# arduinolcd_2020-11-17_19-29-00.net
KiCad netlist of a schematic drawn in EasyEDA
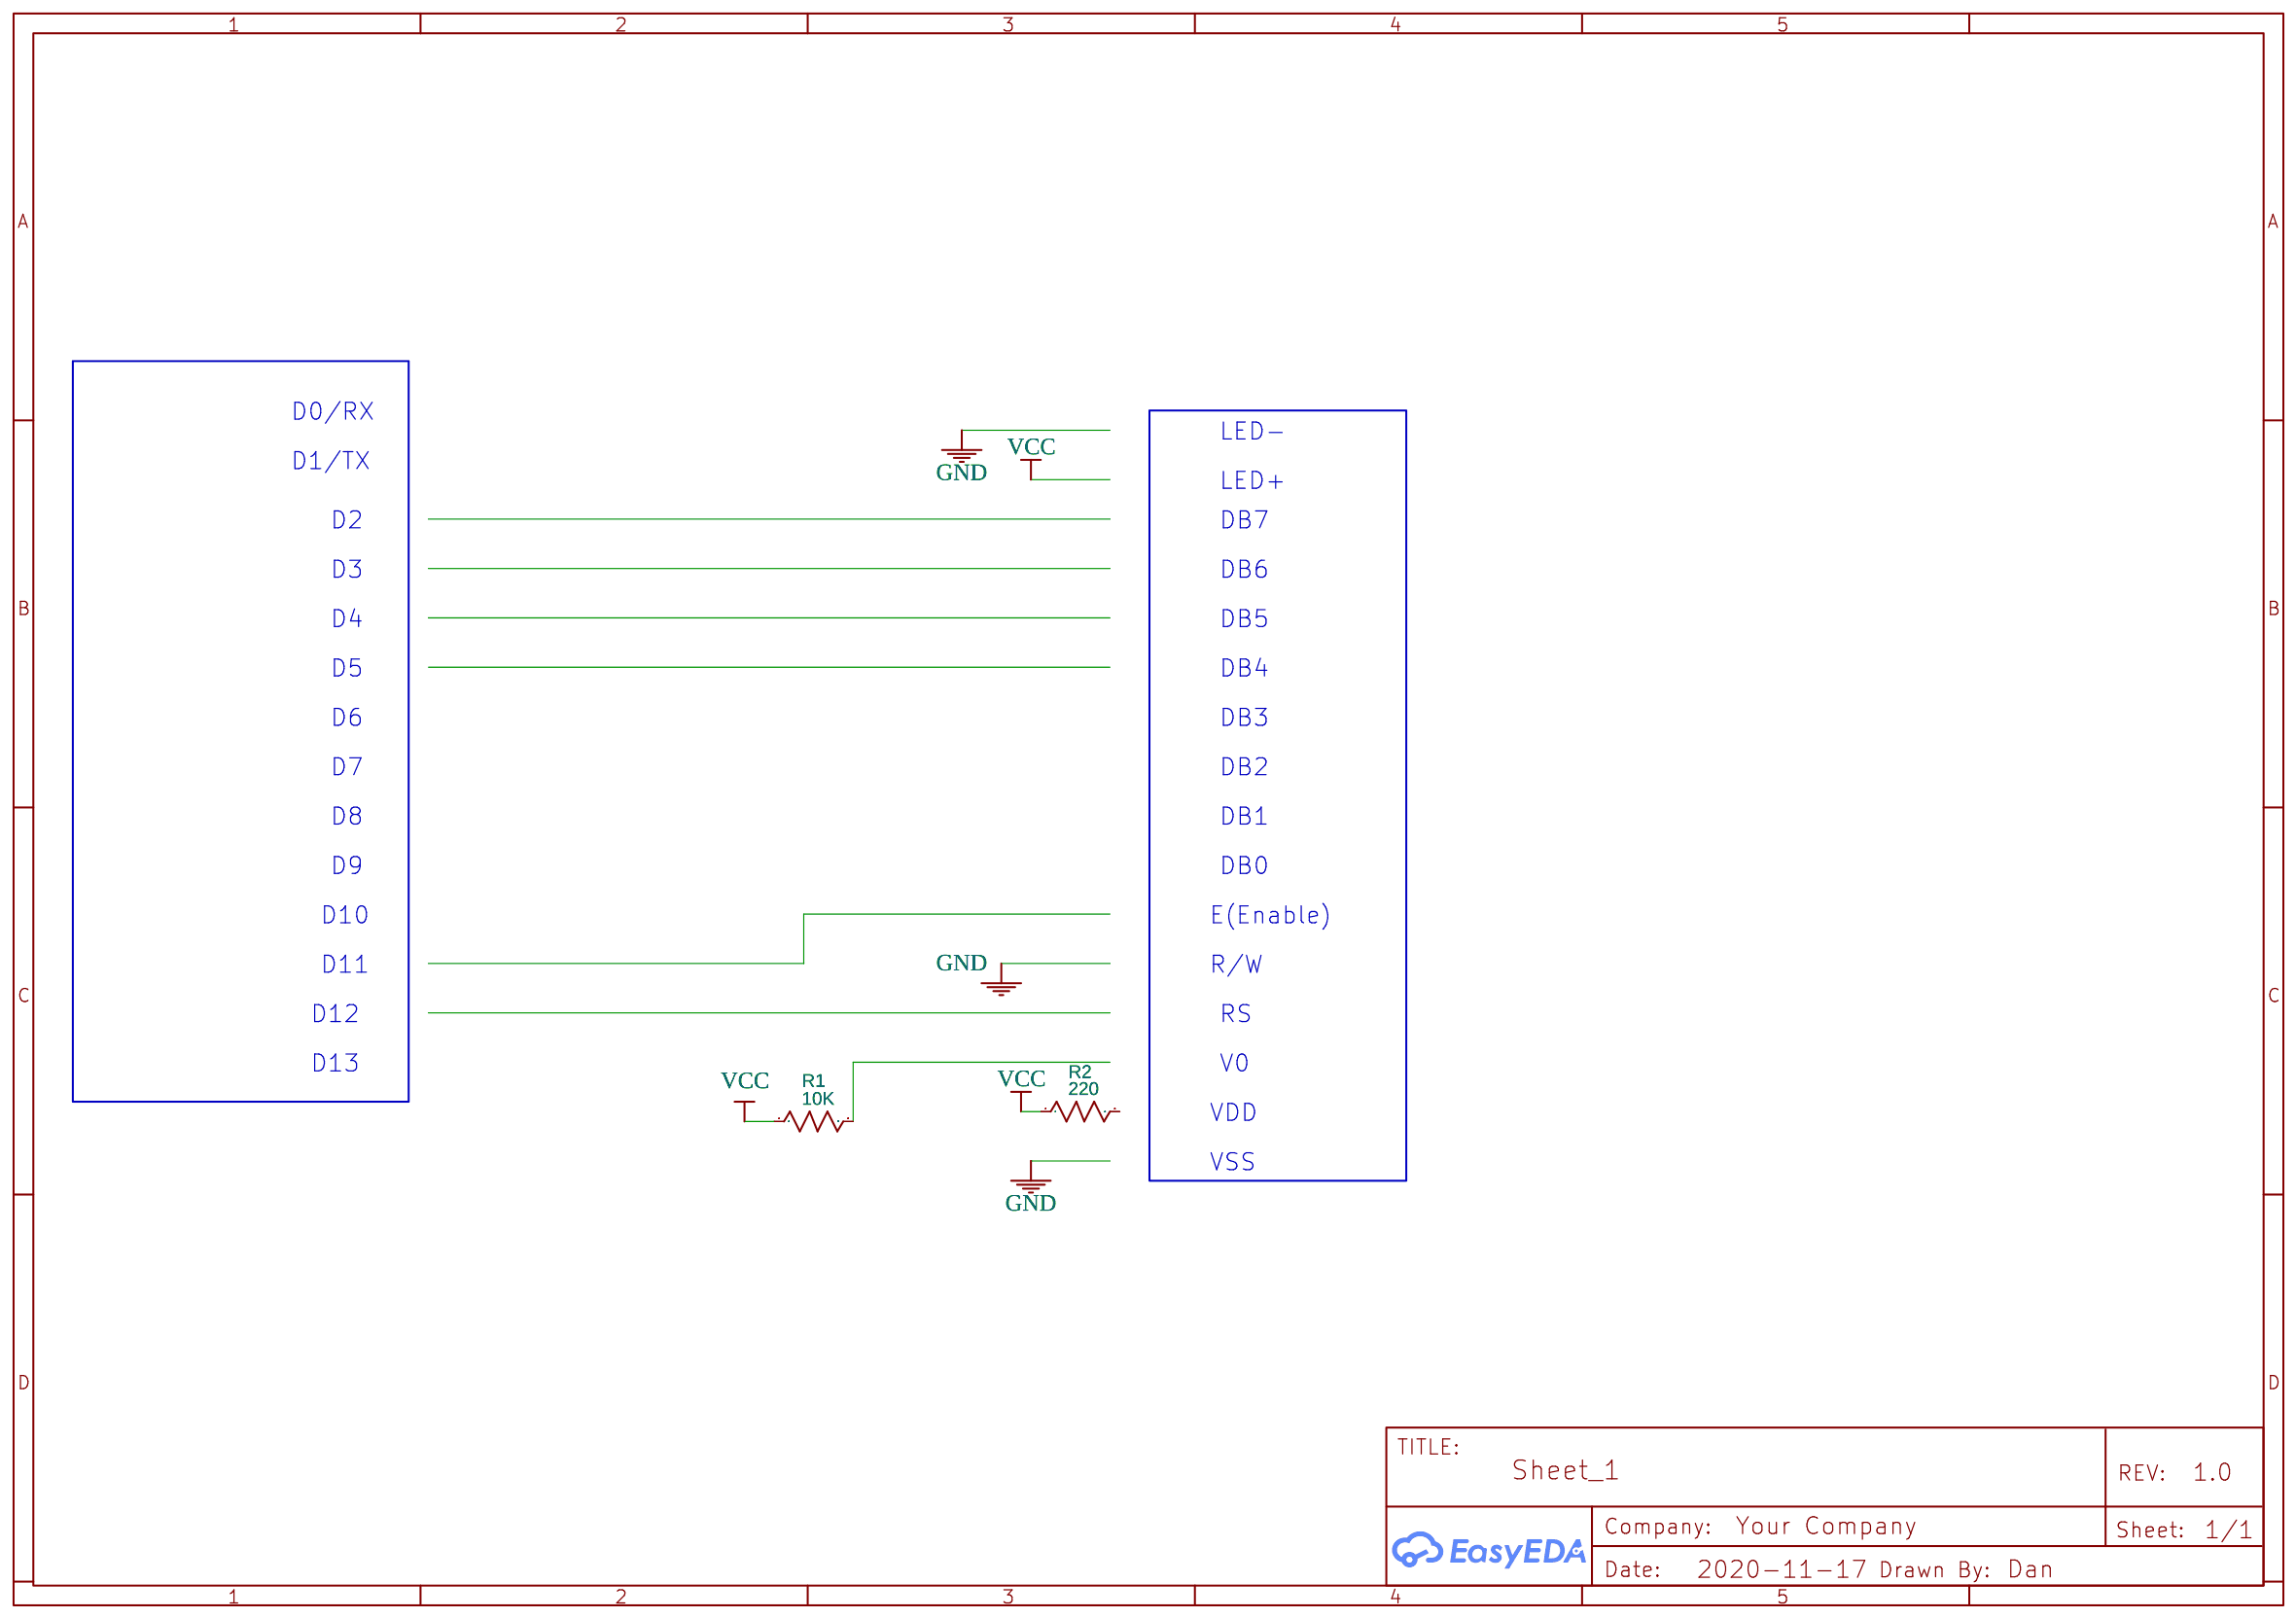
[diagram p0: schematic sheet]

(export (version "E")
  (design (tool "Eeschema 10.0.6"))
  (components
    (comp (ref "R1") (value "10K") (libsource (lib "") (part "R_0603_US")))
    (comp (ref "R2") (value "220") (libsource (lib "") (part "R_0603_US")))
  )
  (nets
    (net (code "2") (name "VCC") (class "Default")
      (node (ref "R1") (pin "1") (pinfunction "1_1") (pintype "unspecified"))
      (node (ref "R2") (pin "1") (pinfunction "1_1") (pintype "unspecified"))
    )
    (net (code "3") (name "unconnected-(R1-Pad2)") (class "Default")
      (node (ref "R1") (pin "2") (pinfunction "2_2") (pintype "unspecified"))
    )
    (net (code "4") (name "unconnected-(R2-Pad2)") (class "Default")
      (node (ref "R2") (pin "2") (pinfunction "2_2") (pintype "unspecified"))
    )
  )
)
